# arm_v2.net
KiCad netlist of a schematic drawn in Altium Designer
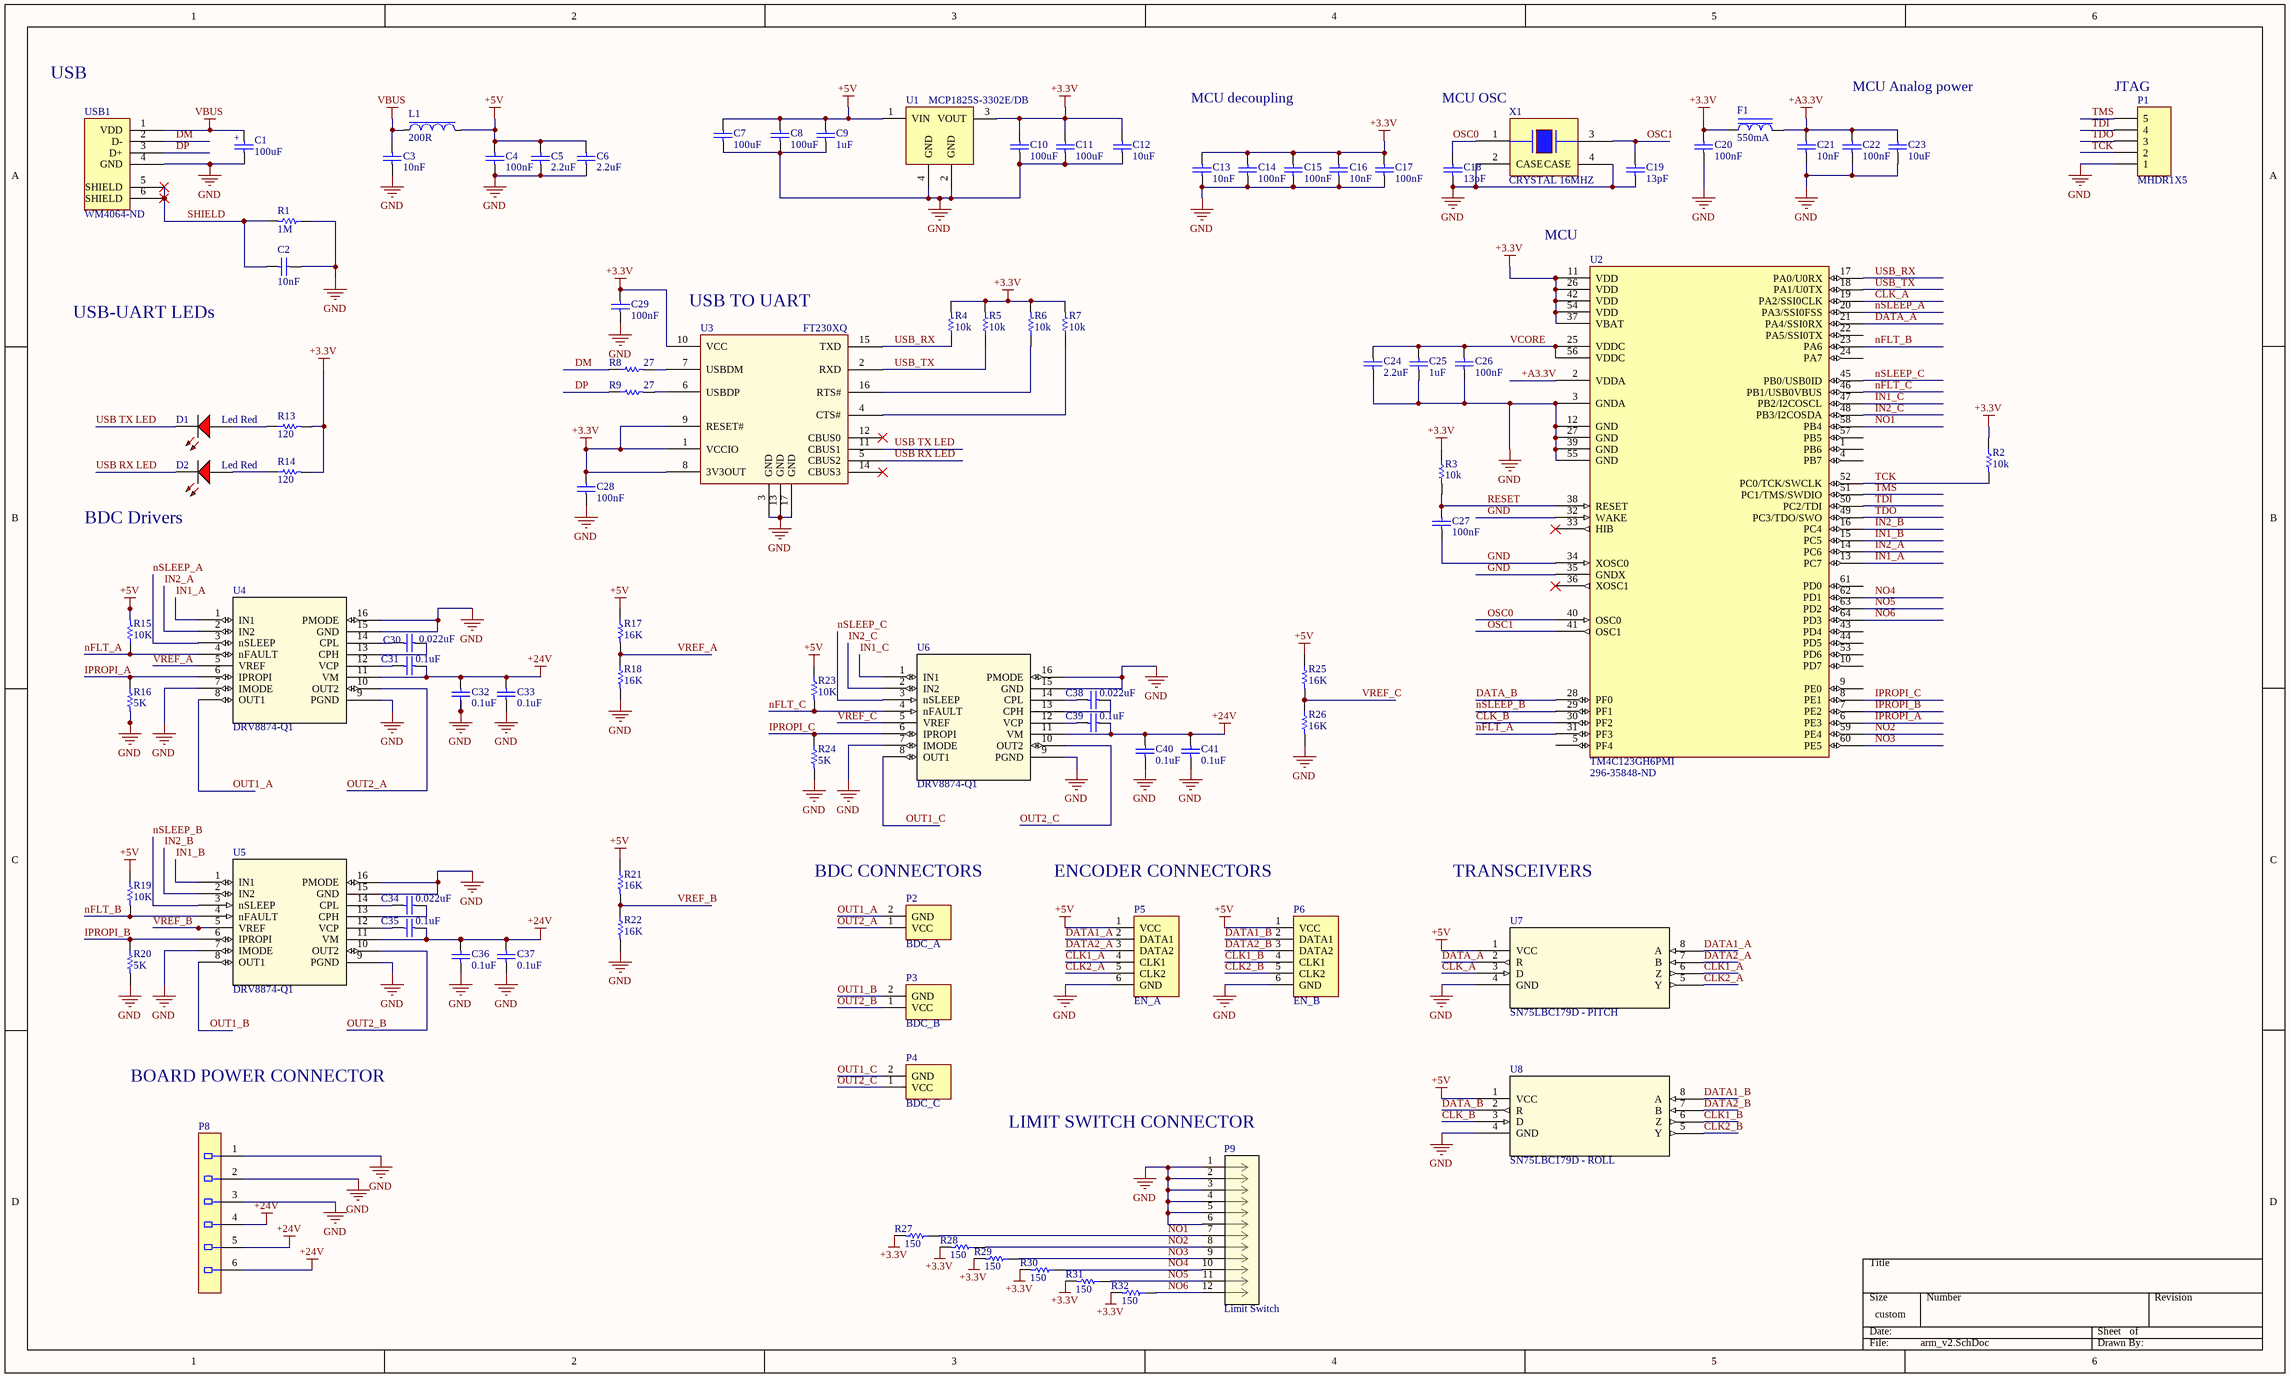
[diagram p0: arm_v2.SchDoc]

(export (version "E")
  (design (tool "Eeschema 10.0.6"))
  (components
    (comp (ref "C1")
      (value "100uF")
      (footprint "CapAlu6.3mmx12.5mm")
      (description "Capacitor 35v 100uF 6.3mm")
      (fields
        (field (name "MANUFACTURER") "Nichicon")
        (field (name "MANUFACTURER PART NUMBER") "UHV1V101MED")
      )
      (libsource (lib "Capacitors") (part "100uF_35v_6.3x12.5"))
    )
    (comp (ref "C2")
      (value "10nF")
      (footprint "CAP_1206")
      (description "CAP CER 10000PF 500V X7R 1206")
      (fields
        (field (name "MANUFACTURER") "Samsung Electro-Mechanics America, Inc")
        (field (name "MANUFACTURER PART NUMBER") "CL31B103KGFNNNE")
      )
      (libsource (lib "Capacitors") (part "10nF_500V_1206"))
    )
    (comp (ref "C3")
      (value "10nF")
      (footprint "CAP_0402_M")
      (description "CAP CER 10000PF 50V 10% X7R 0402")
      (fields
        (field (name "MANUFACTURER") "Kemet")
        (field (name "MANUFACTURER PART NUMBER") "C0402C103K5RACTU")
      )
      (libsource (lib "Capacitors") (part "10nF_50V_0402"))
    )
    (comp (ref "C4")
      (value "100nF")
      (footprint "CAP_0402_M")
      (description "CAP CER 100NF 50V 20% X5R 0402")
      (fields
        (field (name "MANUFACTURER") "TDK Corporation")
        (field (name "MANUFACTURER PART NUMBER") "C1005X5R1H104M050BB")
      )
      (libsource (lib "Capacitors") (part "100nF_50V_0402"))
    )
    (comp (ref "C5")
      (value "2.2uF")
      (footprint "CAP_0402_M")
      (description "CAP CER 2.2UF 10V 20% X5R 0402")
      (fields
        (field (name "MANUFACTURER") "Taiyo Yuden")
        (field (name "MANUFACTURER PART NUMBER") "LMK105BJ225MV-F")
      )
      (libsource (lib "Capacitors") (part "2.2uF_10V_0402"))
    )
    (comp (ref "C6")
      (value "2.2uF")
      (footprint "CAP_0402_M")
      (description "CAP CER 2.2UF 10V 20% X5R 0402")
      (fields
        (field (name "MANUFACTURER") "Taiyo Yuden")
        (field (name "MANUFACTURER PART NUMBER") "LMK105BJ225MV-F")
      )
      (libsource (lib "Capacitors") (part "2.2uF_10V_0402"))
    )
    (comp (ref "C7")
      (value "100uF")
      (footprint "CAP_1206")
      (description "CAP CER 100UF 6.3V X5R 1206")
      (fields
        (field (name "MANUFACTURER") "Murata Electronics North America")
        (field (name "MANUFACTURER PART NUMBER") "GRM31CR60J107ME39L")
      )
      (libsource (lib "Capacitors") (part "100uF_6.3v_1206_X5R"))
    )
    (comp (ref "C8")
      (value "100uF")
      (footprint "CAP_1206")
      (description "CAP CER 100UF 6.3V X5R 1206")
      (fields
        (field (name "MANUFACTURER") "Murata Electronics North America")
        (field (name "MANUFACTURER PART NUMBER") "GRM31CR60J107ME39L")
      )
      (libsource (lib "Capacitors") (part "100uF_6.3v_1206_X5R"))
    )
    (comp (ref "C9")
      (value "1uF")
      (footprint "CAP_0402_M")
      (description "CAP CER 1UF 25V 10% X5R 0402")
      (fields
        (field (name "MANUFACTURER") "TDK Corporation")
        (field (name "MANUFACTURER PART NUMBER") "C1005X5R1E105K050BC")
      )
      (libsource (lib "Capacitors") (part "1uF_25V_0402"))
    )
    (comp (ref "C10")
      (value "100uF")
      (footprint "CAP_1206")
      (description "CAP CER 100UF 6.3V X5R 1206")
      (fields
        (field (name "MANUFACTURER") "Murata Electronics North America")
        (field (name "MANUFACTURER PART NUMBER") "GRM31CR60J107ME39L")
      )
      (libsource (lib "Capacitors") (part "100uF_6.3v_1206_X5R"))
    )
    (comp (ref "C11")
      (value "100uF")
      (footprint "CAP_1206")
      (description "CAP CER 100UF 6.3V X5R 1206")
      (fields
        (field (name "MANUFACTURER") "Murata Electronics North America")
        (field (name "MANUFACTURER PART NUMBER") "GRM31CR60J107ME39L")
      )
      (libsource (lib "Capacitors") (part "100uF_6.3v_1206_X5R"))
    )
    (comp (ref "C12")
      (value "10uF")
      (footprint "CAP_0603")
      (description "CAP CER 10UF 10V 20% X5R 0603")
      (fields
        (field (name "MANUFACTURER") "Taiyo Yuden")
        (field (name "MANUFACTURER PART NUMBER") "LMK107BBJ106MAHT")
      )
      (libsource (lib "Capacitors") (part "10uF_10V_0603"))
    )
    (comp (ref "C13")
      (value "10nF")
      (footprint "CAP_0402_M")
      (description "CAP CER 10000PF 50V 10% X7R 0402")
      (fields
        (field (name "MANUFACTURER") "Kemet")
        (field (name "MANUFACTURER PART NUMBER") "C0402C103K5RACTU")
      )
      (libsource (lib "Capacitors") (part "10nF_50V_0402"))
    )
    (comp (ref "C14")
      (value "100nF")
      (footprint "CAP_0402_M")
      (description "CAP CER 100NF 50V 20% X5R 0402")
      (fields
        (field (name "MANUFACTURER") "TDK Corporation")
        (field (name "MANUFACTURER PART NUMBER") "C1005X5R1H104M050BB")
      )
      (libsource (lib "Capacitors") (part "100nF_50V_0402"))
    )
    (comp (ref "C15")
      (value "100nF")
      (footprint "CAP_0402_M")
      (description "CAP CER 100NF 50V 20% X5R 0402")
      (fields
        (field (name "MANUFACTURER") "TDK Corporation")
        (field (name "MANUFACTURER PART NUMBER") "C1005X5R1H104M050BB")
      )
      (libsource (lib "Capacitors") (part "100nF_50V_0402"))
    )
    (comp (ref "C16")
      (value "10nF")
      (footprint "CAP_0402_M")
      (description "CAP CER 10000PF 50V 10% X7R 0402")
      (fields
        (field (name "MANUFACTURER") "Kemet")
        (field (name "MANUFACTURER PART NUMBER") "C0402C103K5RACTU")
      )
      (libsource (lib "Capacitors") (part "10nF_50V_0402"))
    )
    (comp (ref "C17")
      (value "100nF")
      (footprint "CAP_0402_M")
      (description "CAP CER 100NF 50V 20% X5R 0402")
      (fields
        (field (name "MANUFACTURER") "TDK Corporation")
        (field (name "MANUFACTURER PART NUMBER") "C1005X5R1H104M050BB")
      )
      (libsource (lib "Capacitors") (part "100nF_50V_0402"))
    )
    (comp (ref "C18")
      (value "13pF")
      (footprint "CAP_0402_M")
      (description "CAP CER 13PF 50V 5% NP0 0402")
      (fields
        (field (name "MANUFACTURER") "Samsung Electro-Mechanics America, Inc")
        (field (name "MANUFACTURER PART NUMBER") "CL05C130JB5NNNC")
      )
      (libsource (lib "Capacitors") (part "13pF_50V_0402"))
    )
    (comp (ref "C19")
      (value "13pF")
      (footprint "CAP_0402_M")
      (description "CAP CER 13PF 50V 5% NP0 0402")
      (fields
        (field (name "MANUFACTURER") "Samsung Electro-Mechanics America, Inc")
        (field (name "MANUFACTURER PART NUMBER") "CL05C130JB5NNNC")
      )
      (libsource (lib "Capacitors") (part "13pF_50V_0402"))
    )
    (comp (ref "C20")
      (value "100nF")
      (footprint "CAP_0402_M")
      (description "CAP CER 100NF 50V 20% X5R 0402")
      (fields
        (field (name "MANUFACTURER") "TDK Corporation")
        (field (name "MANUFACTURER PART NUMBER") "C1005X5R1H104M050BB")
      )
      (libsource (lib "Capacitors") (part "100nF_50V_0402"))
    )
    (comp (ref "C21")
      (value "10nF")
      (footprint "CAP_0402_M")
      (description "CAP CER 10000PF 50V 10% X7R 0402")
      (fields
        (field (name "MANUFACTURER") "Kemet")
        (field (name "MANUFACTURER PART NUMBER") "C0402C103K5RACTU")
      )
      (libsource (lib "Capacitors") (part "10nF_50V_0402"))
    )
    (comp (ref "C22")
      (value "100nF")
      (footprint "CAP_0402_M")
      (description "CAP CER 100NF 50V 20% X5R 0402")
      (fields
        (field (name "MANUFACTURER") "TDK Corporation")
        (field (name "MANUFACTURER PART NUMBER") "C1005X5R1H104M050BB")
      )
      (libsource (lib "Capacitors") (part "100nF_50V_0402"))
    )
    (comp (ref "C23")
      (value "10uF")
      (footprint "CAP_0603")
      (description "CAP CER 10UF 10V 20% X5R 0603")
      (fields
        (field (name "MANUFACTURER") "Taiyo Yuden")
        (field (name "MANUFACTURER PART NUMBER") "LMK107BBJ106MAHT")
      )
      (libsource (lib "Capacitors") (part "10uF_10V_0603"))
    )
    (comp (ref "C24")
      (value "2.2uF")
      (footprint "CAP_0603")
      (description "CAP CER 2.2UF 35V 10% X5R 0603")
      (fields
        (field (name "MANUFACTURER") "Murata Electronics North America")
        (field (name "MANUFACTURER PART NUMBER") "GRM188R6YA225KA12D")
      )
      (libsource (lib "Capacitors") (part "2.2uF_35V_0603"))
    )
    (comp (ref "C25")
      (value "1uF")
      (footprint "CAP_0402_M")
      (description "CAP CER 1UF 25V 10% X5R 0402")
      (fields
        (field (name "MANUFACTURER") "TDK Corporation")
        (field (name "MANUFACTURER PART NUMBER") "C1005X5R1E105K050BC")
      )
      (libsource (lib "Capacitors") (part "1uF_25V_0402"))
    )
    (comp (ref "C26")
      (value "100nF")
      (footprint "CAP_0402_M")
      (description "CAP CER 100NF 50V 20% X5R 0402")
      (fields
        (field (name "MANUFACTURER") "TDK Corporation")
        (field (name "MANUFACTURER PART NUMBER") "C1005X5R1H104M050BB")
      )
      (libsource (lib "Capacitors") (part "100nF_50V_0402"))
    )
    (comp (ref "C27")
      (value "100nF")
      (footprint "CAP_0402_M")
      (description "CAP CER 100NF 50V 20% X5R 0402")
      (fields
        (field (name "MANUFACTURER") "TDK Corporation")
        (field (name "MANUFACTURER PART NUMBER") "C1005X5R1H104M050BB")
      )
      (libsource (lib "Capacitors") (part "100nF_50V_0402"))
    )
    (comp (ref "C28")
      (value "100nF")
      (footprint "CAP_0402_M")
      (description "CAP CER 100NF 50V 20% X5R 0402")
      (fields
        (field (name "MANUFACTURER") "TDK Corporation")
        (field (name "MANUFACTURER PART NUMBER") "C1005X5R1H104M050BB")
      )
      (libsource (lib "Capacitors") (part "100nF_50V_0402"))
    )
    (comp (ref "C29")
      (value "100nF")
      (footprint "CAP_0402_M")
      (description "CAP CER 100NF 50V 20% X5R 0402")
      (fields
        (field (name "MANUFACTURER") "TDK Corporation")
        (field (name "MANUFACTURER PART NUMBER") "C1005X5R1H104M050BB")
      )
      (libsource (lib "Capacitors") (part "100nF_50V_0402"))
    )
    (comp (ref "C30")
      (value "0.022uF")
      (footprint "CAP_0402_M")
      (description "CAP CER 100NF 50V 20% X5R 0402")
      (fields
        (field (name "MANUFACTURER") "TDK Corporation")
        (field (name "MANUFACTURER PART NUMBER") "C1005X5R1H104M050BB")
      )
      (libsource (lib "Capacitors") (part "100nF_50V_0402"))
    )
    (comp (ref "C31")
      (value "0.1uF")
      (footprint "CAP_0402_M")
      (description "CAP CER 100NF 50V 20% X5R 0402")
      (fields
        (field (name "MANUFACTURER") "TDK Corporation")
        (field (name "MANUFACTURER PART NUMBER") "C1005X5R1H104M050BB")
      )
      (libsource (lib "Capacitors") (part "100nF_50V_0402"))
    )
    (comp (ref "C32")
      (value "0.1uF")
      (footprint "CAP_0402_M")
      (description "CAP CER 100NF 50V 20% X5R 0402")
      (fields
        (field (name "MANUFACTURER") "TDK Corporation")
        (field (name "MANUFACTURER PART NUMBER") "C1005X5R1H104M050BB")
      )
      (libsource (lib "Capacitors") (part "100nF_50V_0402"))
    )
    (comp (ref "C33")
      (value "0.1uF")
      (footprint "CAP_0402_M")
      (description "CAP CER 100NF 50V 20% X5R 0402")
      (fields
        (field (name "MANUFACTURER") "TDK Corporation")
        (field (name "MANUFACTURER PART NUMBER") "C1005X5R1H104M050BB")
      )
      (libsource (lib "Capacitors") (part "100nF_50V_0402"))
    )
    (comp (ref "C34")
      (value "0.022uF")
      (footprint "CAP_0402_M")
      (description "CAP CER 100NF 50V 20% X5R 0402")
      (fields
        (field (name "MANUFACTURER") "TDK Corporation")
        (field (name "MANUFACTURER PART NUMBER") "C1005X5R1H104M050BB")
      )
      (libsource (lib "Capacitors") (part "100nF_50V_0402"))
    )
    (comp (ref "C35")
      (value "0.1uF")
      (footprint "CAP_0402_M")
      (description "CAP CER 100NF 50V 20% X5R 0402")
      (fields
        (field (name "MANUFACTURER") "TDK Corporation")
        (field (name "MANUFACTURER PART NUMBER") "C1005X5R1H104M050BB")
      )
      (libsource (lib "Capacitors") (part "100nF_50V_0402"))
    )
    (comp (ref "C36")
      (value "0.1uF")
      (footprint "CAP_0402_M")
      (description "CAP CER 100NF 50V 20% X5R 0402")
      (fields
        (field (name "MANUFACTURER") "TDK Corporation")
        (field (name "MANUFACTURER PART NUMBER") "C1005X5R1H104M050BB")
      )
      (libsource (lib "Capacitors") (part "100nF_50V_0402"))
    )
    (comp (ref "C37")
      (value "0.1uF")
      (footprint "CAP_0402_M")
      (description "CAP CER 100NF 50V 20% X5R 0402")
      (fields
        (field (name "MANUFACTURER") "TDK Corporation")
        (field (name "MANUFACTURER PART NUMBER") "C1005X5R1H104M050BB")
      )
      (libsource (lib "Capacitors") (part "100nF_50V_0402"))
    )
    (comp (ref "C38")
      (value "0.022uF")
      (footprint "CAP_0402_M")
      (description "CAP CER 100NF 50V 20% X5R 0402")
      (fields
        (field (name "MANUFACTURER") "TDK Corporation")
        (field (name "MANUFACTURER PART NUMBER") "C1005X5R1H104M050BB")
      )
      (libsource (lib "Capacitors") (part "100nF_50V_0402"))
    )
    (comp (ref "C39")
      (value "0.1uF")
      (footprint "CAP_0402_M")
      (description "CAP CER 100NF 50V 20% X5R 0402")
      (fields
        (field (name "MANUFACTURER") "TDK Corporation")
        (field (name "MANUFACTURER PART NUMBER") "C1005X5R1H104M050BB")
      )
      (libsource (lib "Capacitors") (part "100nF_50V_0402"))
    )
    (comp (ref "C40")
      (value "0.1uF")
      (footprint "CAP_0402_M")
      (description "CAP CER 100NF 50V 20% X5R 0402")
      (fields
        (field (name "MANUFACTURER") "TDK Corporation")
        (field (name "MANUFACTURER PART NUMBER") "C1005X5R1H104M050BB")
      )
      (libsource (lib "Capacitors") (part "100nF_50V_0402"))
    )
    (comp (ref "C41")
      (value "0.1uF")
      (footprint "CAP_0402_M")
      (description "CAP CER 100NF 50V 20% X5R 0402")
      (fields
        (field (name "MANUFACTURER") "TDK Corporation")
        (field (name "MANUFACTURER PART NUMBER") "C1005X5R1H104M050BB")
      )
      (libsource (lib "Capacitors") (part "100nF_50V_0402"))
    )
    (comp (ref "D1")
      (value "Led Red")
      (footprint "TOPLED 0805")
      (description "LED TOPLED 630NM SUP RED CLR SMD")
      (fields
        (field (name "MANUFACTURER") "OSRAM Opto Semiconductors Inc")
        (field (name "MANUFACTURER PART NUMBER") "LS M67K-H2L1-1-Z")
      )
      (libsource (lib "Diodes") (part "TOPLED 0803"))
    )
    (comp (ref "D2")
      (value "Led Red")
      (footprint "TOPLED 0805")
      (description "LED TOPLED 630NM SUP RED CLR SMD")
      (fields
        (field (name "MANUFACTURER") "OSRAM Opto Semiconductors Inc")
        (field (name "MANUFACTURER PART NUMBER") "LS M67K-H2L1-1-Z")
      )
      (libsource (lib "Diodes") (part "TOPLED 0803"))
    )
    (comp (ref "F1")
      (value "550mA")
      (footprint "RES_0402_M")
      (description "FERRITE CHIP 40 OHM 550MA 0402")
      (fields
        (field (name "MANUFACTURER") "TDK Corporation")
        (field (name "MANUFACTURER PART NUMBER") "MMZ1005Y400CT000")
      )
      (libsource (lib "Resistors") (part "40O_550mA_0402"))
    )
    (comp (ref "L1")
      (value "200R")
      (footprint "IND_0603")
      (description "FILTER CHIP 220 OHM 2A 0603")
      (fields
        (field (name "MANUFACTURER") "Murata Electronics North America")
        (field (name "MANUFACTURER PART NUMBER") "BLM18EG221SN1D")
      )
      (libsource (lib "Inductors") (part "Ferrite_200 ohms_2A"))
    )
    (comp (ref "P1")
      (value "MHDR1X5")
      (footprint "MHDR1X5")
      (description "Header, 5-Pin")
      (fields (field (name "PUBLISHER") "Altium Limited"))
      (libsource (lib "Miscellaneous Connectors") (part "MHDR1X5"))
    )
    (comp (ref "P2")
      (value "BDC_A")
      (footprint "SamacSys:436500227")
      (description "Connector")
      (fields (field (name "MANUFACTURER_PART_NUMBER") "43650-0227"))
      (libsource (lib "*") (part "43650-0227"))
    )
    (comp (ref "P3")
      (value "BDC_B")
      (footprint "SamacSys:436500227")
      (description "Connector")
      (fields (field (name "MANUFACTURER_PART_NUMBER") "43650-0227"))
      (libsource (lib "*") (part "43650-0227"))
    )
    (comp (ref "P4")
      (value "BDC_C")
      (footprint "SamacSys:436500227")
      (description "Connector")
      (fields (field (name "MANUFACTURER_PART_NUMBER") "43650-0227"))
      (libsource (lib "*") (part "43650-0227"))
    )
    (comp (ref "P5")
      (value "EN_A")
      (footprint "SamacSys:1053091106")
      (description "Connector")
      (fields (field (name "MANUFACTURER_PART_NUMBER") "105309-1106"))
      (libsource (lib "*") (part "105309-1106"))
    )
    (comp (ref "P6")
      (value "EN_B")
      (footprint "SamacSys:1053091106")
      (description "Connector")
      (fields (field (name "MANUFACTURER_PART_NUMBER") "105309-1106"))
      (libsource (lib "*") (part "105309-1106"))
    )
    (comp (ref "P8") (value "76825-0006") (libsource (lib "Molex 76825-0006") (part "76825-0006")))
    (comp (ref "P9")
      (value "Limit Switch")
      (footprint "CON_1053141112")
      (description "No Description Available")
      (fields
        (field (name "MANUFACTURER_PART_NUMBER") "1053141112")
        (field (name "COPYRIGHT") "Copyright (C) 2018 Accelerated Designs. All rights reserved")
      )
      (libsource (lib "Molex 1053141112") (part "1053141112"))
    )
    (comp (ref "R1")
      (value "1M")
      (footprint "RES_1206")
      (description "RES SMD 1M OHM 5% 1/4W 1206")
      (fields
        (field (name "MANUFACTURER") "Panasonic Electronic Components")
        (field (name "MANUFACTURER PART NUMBER") "ERJ-8GEYJ105V")
      )
      (libsource (lib "Resistors") (part "1M_5%_1206"))
    )
    (comp (ref "R2")
      (value "10k")
      (footprint "RES_0402_M")
      (description "RES SMD 10K OHM 1% 1/10W 0402")
      (fields
        (field (name "MANUFACTURER") "Panasonic Electronic Components")
        (field (name "MANUFACTURER PART NUMBER") "ERJ-2RKF1002X")
      )
      (libsource (lib "Resistors") (part "10k_1%_0402"))
    )
    (comp (ref "R3")
      (value "10k")
      (footprint "RES_0402_M")
      (description "RES SMD 10K OHM 1% 1/10W 0402")
      (fields
        (field (name "MANUFACTURER") "Panasonic Electronic Components")
        (field (name "MANUFACTURER PART NUMBER") "ERJ-2RKF1002X")
      )
      (libsource (lib "Resistors") (part "10k_1%_0402"))
    )
    (comp (ref "R4")
      (value "10k")
      (footprint "RES_0402_M")
      (description "RES SMD 10K OHM 1% 1/10W 0402")
      (fields
        (field (name "MANUFACTURER") "Panasonic Electronic Components")
        (field (name "MANUFACTURER PART NUMBER") "ERJ-2RKF1002X")
      )
      (libsource (lib "Resistors") (part "10k_1%_0402"))
    )
    (comp (ref "R5")
      (value "10k")
      (footprint "RES_0402_M")
      (description "RES SMD 10K OHM 1% 1/10W 0402")
      (fields
        (field (name "MANUFACTURER") "Panasonic Electronic Components")
        (field (name "MANUFACTURER PART NUMBER") "ERJ-2RKF1002X")
      )
      (libsource (lib "Resistors") (part "10k_1%_0402"))
    )
    (comp (ref "R6")
      (value "10k")
      (footprint "RES_0402_M")
      (description "RES SMD 10K OHM 1% 1/10W 0402")
      (fields
        (field (name "MANUFACTURER") "Panasonic Electronic Components")
        (field (name "MANUFACTURER PART NUMBER") "ERJ-2RKF1002X")
      )
      (libsource (lib "Resistors") (part "10k_1%_0402"))
    )
    (comp (ref "R7")
      (value "10k")
      (footprint "RES_0402_M")
      (description "RES SMD 10K OHM 1% 1/10W 0402")
      (fields
        (field (name "MANUFACTURER") "Panasonic Electronic Components")
        (field (name "MANUFACTURER PART NUMBER") "ERJ-2RKF1002X")
      )
      (libsource (lib "Resistors") (part "10k_1%_0402"))
    )
    (comp (ref "R8")
      (value "27")
      (footprint "RES_0402_M")
      (description "RES SMD 27 OHM 1% 1/10W 0402")
      (fields
        (field (name "MANUFACTURER") "Panasonic Electronic Components")
        (field (name "MANUFACTURER PART NUMBER") "ERJ-2RKF27R0X")
      )
      (libsource (lib "Resistors") (part "27_1%_0402"))
    )
    (comp (ref "R9")
      (value "27")
      (footprint "RES_0402_M")
      (description "RES SMD 27 OHM 1% 1/10W 0402")
      (fields
        (field (name "MANUFACTURER") "Panasonic Electronic Components")
        (field (name "MANUFACTURER PART NUMBER") "ERJ-2RKF27R0X")
      )
      (libsource (lib "Resistors") (part "27_1%_0402"))
    )
    (comp (ref "R13")
      (value "120")
      (footprint "RES_0402_M")
      (description "RES SMD 120 OHM 1% 1/10W 0402")
      (fields
        (field (name "MANUFACTURER") "Panasonic Electronic Components")
        (field (name "MANUFACTURER PART NUMBER") "ERJ-2RKF1200X")
      )
      (libsource (lib "Resistors") (part "120_1%_0402"))
    )
    (comp (ref "R14")
      (value "120")
      (footprint "RES_0402_M")
      (description "RES SMD 120 OHM 1% 1/10W 0402")
      (fields
        (field (name "MANUFACTURER") "Panasonic Electronic Components")
        (field (name "MANUFACTURER PART NUMBER") "ERJ-2RKF1200X")
      )
      (libsource (lib "Resistors") (part "120_1%_0402"))
    )
    (comp (ref "R15")
      (value "10K")
      (footprint "RES_0402_M")
      (description "RES SMD 0 OHM JUMPER 1/16W 0402")
      (fields
        (field (name "MANUFACTURER") "Yageo")
        (field (name "MANUFACTURER PART NUMBER") "RC0402FR-070RL")
      )
      (libsource (lib "Resistors") (part "0_0402"))
    )
    (comp (ref "R16")
      (value "5K")
      (footprint "RES_0402_M")
      (description "RES SMD 0 OHM JUMPER 1/16W 0402")
      (fields
        (field (name "MANUFACTURER") "Yageo")
        (field (name "MANUFACTURER PART NUMBER") "RC0402FR-070RL")
      )
      (libsource (lib "Resistors") (part "0_0402"))
    )
    (comp (ref "R17")
      (value "16K")
      (footprint "RES_0402_M")
      (description "RES SMD 0 OHM JUMPER 1/16W 0402")
      (fields
        (field (name "MANUFACTURER") "Yageo")
        (field (name "MANUFACTURER PART NUMBER") "RC0402FR-070RL")
      )
      (libsource (lib "Resistors") (part "0_0402"))
    )
    (comp (ref "R18")
      (value "16K")
      (footprint "RES_0402_M")
      (description "RES SMD 0 OHM JUMPER 1/16W 0402")
      (fields
        (field (name "MANUFACTURER") "Yageo")
        (field (name "MANUFACTURER PART NUMBER") "RC0402FR-070RL")
      )
      (libsource (lib "Resistors") (part "0_0402"))
    )
    (comp (ref "R19")
      (value "10K")
      (footprint "RES_0402_M")
      (description "RES SMD 0 OHM JUMPER 1/16W 0402")
      (fields
        (field (name "MANUFACTURER") "Yageo")
        (field (name "MANUFACTURER PART NUMBER") "RC0402FR-070RL")
      )
      (libsource (lib "Resistors") (part "0_0402"))
    )
    (comp (ref "R20")
      (value "5K")
      (footprint "RES_0402_M")
      (description "RES SMD 0 OHM JUMPER 1/16W 0402")
      (fields
        (field (name "MANUFACTURER") "Yageo")
        (field (name "MANUFACTURER PART NUMBER") "RC0402FR-070RL")
      )
      (libsource (lib "Resistors") (part "0_0402"))
    )
    (comp (ref "R21")
      (value "16K")
      (footprint "RES_0402_M")
      (description "RES SMD 0 OHM JUMPER 1/16W 0402")
      (fields
        (field (name "MANUFACTURER") "Yageo")
        (field (name "MANUFACTURER PART NUMBER") "RC0402FR-070RL")
      )
      (libsource (lib "Resistors") (part "0_0402"))
    )
    (comp (ref "R22")
      (value "16K")
      (footprint "RES_0402_M")
      (description "RES SMD 0 OHM JUMPER 1/16W 0402")
      (fields
        (field (name "MANUFACTURER") "Yageo")
        (field (name "MANUFACTURER PART NUMBER") "RC0402FR-070RL")
      )
      (libsource (lib "Resistors") (part "0_0402"))
    )
    (comp (ref "R23")
      (value "10K")
      (footprint "RES_0402_M")
      (description "RES SMD 0 OHM JUMPER 1/16W 0402")
      (fields
        (field (name "MANUFACTURER") "Yageo")
        (field (name "MANUFACTURER PART NUMBER") "RC0402FR-070RL")
      )
      (libsource (lib "Resistors") (part "0_0402"))
    )
    (comp (ref "R24")
      (value "5K")
      (footprint "RES_0402_M")
      (description "RES SMD 0 OHM JUMPER 1/16W 0402")
      (fields
        (field (name "MANUFACTURER") "Yageo")
        (field (name "MANUFACTURER PART NUMBER") "RC0402FR-070RL")
      )
      (libsource (lib "Resistors") (part "0_0402"))
    )
    (comp (ref "R25")
      (value "16K")
      (footprint "RES_0402_M")
      (description "RES SMD 0 OHM JUMPER 1/16W 0402")
      (fields
        (field (name "MANUFACTURER") "Yageo")
        (field (name "MANUFACTURER PART NUMBER") "RC0402FR-070RL")
      )
      (libsource (lib "Resistors") (part "0_0402"))
    )
    (comp (ref "R26")
      (value "16K")
      (footprint "RES_0402_M")
      (description "RES SMD 0 OHM JUMPER 1/16W 0402")
      (fields
        (field (name "MANUFACTURER") "Yageo")
        (field (name "MANUFACTURER PART NUMBER") "RC0402FR-070RL")
      )
      (libsource (lib "Resistors") (part "0_0402"))
    )
    (comp (ref "R27")
      (value "150")
      (footprint "RES_0402_M")
      (description "RES SMD 10K OHM 1% 1/10W 0402")
      (fields
        (field (name "MANUFACTURER") "Panasonic Electronic Components")
        (field (name "MANUFACTURER PART NUMBER") "ERJ-2RKF1002X")
      )
      (libsource (lib "Resistors") (part "10k_1%_0402"))
    )
    (comp (ref "R28")
      (value "150")
      (footprint "RES_0402_M")
      (description "RES SMD 10K OHM 1% 1/10W 0402")
      (fields
        (field (name "MANUFACTURER") "Panasonic Electronic Components")
        (field (name "MANUFACTURER PART NUMBER") "ERJ-2RKF1002X")
      )
      (libsource (lib "Resistors") (part "10k_1%_0402"))
    )
    (comp (ref "R29")
      (value "150")
      (footprint "RES_0402_M")
      (description "RES SMD 10K OHM 1% 1/10W 0402")
      (fields
        (field (name "MANUFACTURER") "Panasonic Electronic Components")
        (field (name "MANUFACTURER PART NUMBER") "ERJ-2RKF1002X")
      )
      (libsource (lib "Resistors") (part "10k_1%_0402"))
    )
    (comp (ref "R30")
      (value "150")
      (footprint "RES_0402_M")
      (description "RES SMD 10K OHM 1% 1/10W 0402")
      (fields
        (field (name "MANUFACTURER") "Panasonic Electronic Components")
        (field (name "MANUFACTURER PART NUMBER") "ERJ-2RKF1002X")
      )
      (libsource (lib "Resistors") (part "10k_1%_0402"))
    )
    (comp (ref "R31")
      (value "150")
      (footprint "RES_0402_M")
      (description "RES SMD 10K OHM 1% 1/10W 0402")
      (fields
        (field (name "MANUFACTURER") "Panasonic Electronic Components")
        (field (name "MANUFACTURER PART NUMBER") "ERJ-2RKF1002X")
      )
      (libsource (lib "Resistors") (part "10k_1%_0402"))
    )
    (comp (ref "R32")
      (value "150")
      (footprint "RES_0402_M")
      (description "RES SMD 10K OHM 1% 1/10W 0402")
      (fields
        (field (name "MANUFACTURER") "Panasonic Electronic Components")
        (field (name "MANUFACTURER PART NUMBER") "ERJ-2RKF1002X")
      )
      (libsource (lib "Resistors") (part "10k_1%_0402"))
    )
    (comp (ref "U1")
      (value "MCP1825S-3302E/DB")
      (footprint "SOT230P700X180-4N")
      (description "500 mA, Low Voltage, Low Quiescent Current LDO Regulator")
      (fields (field (name "MANUFACTURER") "Microchip Technology"))
      (libsource (lib "ICs") (part "MCP1825S-3302E/DB"))
    )
    (comp (ref "U2")
      (value "TM4C123GH6PMI")
      (footprint "TSQFP50P1200X1200X120-64N")
      (description "Tiva TM4C123GH6PM Microcontroller ARM Cortex 80 MHz FPU")
      (fields (field (name "SUPPLIER PART NUMBER 1") "296-35848-ND"))
      (libsource (lib "ICs") (part "TM4C123GH6PMI"))
    )
    (comp (ref "U3")
      (value "FT230XQ")
      (footprint "QFN65P400X400X80_HS-17N")
      (description "IC USB SERIAL BASIC UART 16QFN")
      (fields
        (field (name "MANUFACTURER") "FTDI, Future Technology Devices International Ltd")
        (field (name "MANUFACTURER PART NUMBER") "FT230XQ-R")
      )
      (libsource (lib "ICs") (part "FT230XQ-R"))
    )
    (comp (ref "U4")
      (value "DRV8874-Q1")
      (footprint "SOIC_PWPRQ1_TEX")
      (description "No Description Available")
      (fields
        (field (name "MANUFACTURER_PART_NUMBER") "DRV8876QPWPRQ1")
        (field (name "COPYRIGHT") "Copyright (C) 2018 Accelerated Designs. All rights reserved")
      )
      (libsource (lib "DRV8876") (part "DRV8876QPWPRQ1"))
    )
    (comp (ref "U5")
      (value "DRV8874-Q1")
      (footprint "SOIC_PWPRQ1_TEX")
      (description "No Description Available")
      (fields
        (field (name "MANUFACTURER_PART_NUMBER") "DRV8876QPWPRQ1")
        (field (name "COPYRIGHT") "Copyright (C) 2018 Accelerated Designs. All rights reserved")
      )
      (libsource (lib "DRV8876") (part "DRV8876QPWPRQ1"))
    )
    (comp (ref "U6")
      (value "DRV8874-Q1")
      (footprint "SOIC_PWPRQ1_TEX")
      (description "No Description Available")
      (fields
        (field (name "MANUFACTURER_PART_NUMBER") "DRV8876QPWPRQ1")
        (field (name "COPYRIGHT") "Copyright (C) 2018 Accelerated Designs. All rights reserved")
      )
      (libsource (lib "DRV8876") (part "DRV8876QPWPRQ1"))
    )
    (comp (ref "U7")
      (value "SN75LBC179D - PITCH")
      (footprint "D8")
      (description "Low-Power Differential Line Driver And Receiver Pair")
      (fields
        (field (name "MANUFACTURER") "Texas Instruments")
        (field (name "GENERIC_PART_NUMBER") "SN75LBC179")
        (field (name "COPYRIGHT") "Copyright (C) 2018 Accelerated Designs. All rights reserved")
      )
      (libsource (lib "SN75LBC179DR") (part "SN75LBC179D"))
    )
    (comp (ref "U8")
      (value "SN75LBC179D - ROLL")
      (footprint "D8")
      (description "Low-Power Differential Line Driver And Receiver Pair")
      (fields
        (field (name "MANUFACTURER") "Texas Instruments")
        (field (name "GENERIC_PART_NUMBER") "SN75LBC179")
        (field (name "COPYRIGHT") "Copyright (C) 2018 Accelerated Designs. All rights reserved")
      )
      (libsource (lib "SN75LBC179DR") (part "SN75LBC179D"))
    )
    (comp (ref "USB1")
      (value "USB type-B jack")
      (footprint "USB2.5-2H4E")
      (fields (field (name "SUPPLIER PART NUMBER 1") "WM4064-ND"))
      (libsource (lib "Connectors") (part "MOLEX 0670688010"))
    )
    (comp (ref "X1")
      (value "CRYSTAL 16MHZ")
      (footprint "CRYSTAL_3.2x2.5")
      (description "CRYSTAL 16MHZ 20PF SMD")
      (fields
        (field (name "MANUFACTURER") "CTS-Frequency Controls")
        (field (name "MANUFACTURER PART NUMBER") "403C35E16M00000")
      )
      (libsource (lib "ICs") (part "403C35E16M00000"))
    )
  )
  (nets
    (net (code "1") (name "+3.3V") (class "Default")
      (node (ref "C10") (pin "1") (pinfunction "1_1") (pintype "passive"))
      (node (ref "C11") (pin "1") (pinfunction "1_1") (pintype "passive"))
      (node (ref "C12") (pin "1") (pinfunction "1_1") (pintype "passive"))
      (node (ref "C13") (pin "2") (pinfunction "2_2") (pintype "passive"))
      (node (ref "C14") (pin "2") (pinfunction "2_2") (pintype "passive"))
      (node (ref "C15") (pin "2") (pinfunction "2_2") (pintype "passive"))
      (node (ref "C16") (pin "2") (pinfunction "2_2") (pintype "passive"))
      (node (ref "C17") (pin "2") (pinfunction "2_2") (pintype "passive"))
      (node (ref "C20") (pin "2") (pinfunction "2_2") (pintype "passive"))
      (node (ref "C28") (pin "2") (pinfunction "2_2") (pintype "passive"))
      (node (ref "C29") (pin "2") (pinfunction "2_2") (pintype "passive"))
      (node (ref "F1") (pin "1") (pinfunction "1_1") (pintype "passive"))
      (node (ref "R13") (pin "2") (pinfunction "2_2") (pintype "passive"))
      (node (ref "R14") (pin "2") (pinfunction "2_2") (pintype "passive"))
      (node (ref "R2") (pin "1") (pinfunction "1_1") (pintype "passive"))
      (node (ref "R27") (pin "2") (pinfunction "2_2") (pintype "passive"))
      (node (ref "R28") (pin "2") (pinfunction "2_2") (pintype "passive"))
      (node (ref "R29") (pin "2") (pinfunction "2_2") (pintype "passive"))
      (node (ref "R3") (pin "1") (pinfunction "1_1") (pintype "passive"))
      (node (ref "R30") (pin "2") (pinfunction "2_2") (pintype "passive"))
      (node (ref "R31") (pin "2") (pinfunction "2_2") (pintype "passive"))
      (node (ref "R32") (pin "2") (pinfunction "2_2") (pintype "passive"))
      (node (ref "R4") (pin "2") (pinfunction "2_2") (pintype "passive"))
      (node (ref "R5") (pin "2") (pinfunction "2_2") (pintype "passive"))
      (node (ref "R6") (pin "2") (pinfunction "2_2") (pintype "passive"))
      (node (ref "R7") (pin "2") (pinfunction "2_2") (pintype "passive"))
      (node (ref "U1") (pin "3") (pinfunction "VOUT_3") (pintype "power_in"))
      (node (ref "U2") (pin "11") (pinfunction "VDD_11") (pintype "power_in"))
      (node (ref "U2") (pin "26") (pinfunction "VDD_26") (pintype "power_in"))
      (node (ref "U2") (pin "37") (pinfunction "VBAT_37") (pintype "power_in"))
      (node (ref "U2") (pin "42") (pinfunction "VDD_42") (pintype "power_in"))
      (node (ref "U2") (pin "54") (pinfunction "VDD_54") (pintype "power_in"))
      (node (ref "U3") (pin "1") (pinfunction "VCCIO_1") (pintype "passive"))
      (node (ref "U3") (pin "10") (pinfunction "VCC_10") (pintype "passive"))
      (node (ref "U3") (pin "8") (pinfunction "3V3OUT_8") (pintype "passive"))
      (node (ref "U3") (pin "9") (pinfunction "RESET#_9") (pintype "passive"))
    )
    (net (code "2") (name "+5V") (class "Default")
      (node (ref "C4") (pin "2") (pinfunction "2_2") (pintype "passive"))
      (node (ref "C5") (pin "2") (pinfunction "2_2") (pintype "passive"))
      (node (ref "C6") (pin "2") (pinfunction "2_2") (pintype "passive"))
      (node (ref "C7") (pin "1") (pinfunction "1_1") (pintype "passive"))
      (node (ref "C8") (pin "1") (pinfunction "1_1") (pintype "passive"))
      (node (ref "C9") (pin "2") (pinfunction "2_2") (pintype "passive"))
      (node (ref "L1") (pin "2") (pinfunction "2_2") (pintype "passive"))
      (node (ref "P5") (pin "1") (pinfunction "VCC_1") (pintype "passive"))
      (node (ref "P6") (pin "1") (pinfunction "VCC_1") (pintype "passive"))
      (node (ref "R15") (pin "2") (pinfunction "2_2") (pintype "passive"))
      (node (ref "R17") (pin "1") (pinfunction "1_1") (pintype "passive"))
      (node (ref "R19") (pin "1") (pinfunction "1_1") (pintype "passive"))
      (node (ref "R21") (pin "1") (pinfunction "1_1") (pintype "passive"))
      (node (ref "R23") (pin "1") (pinfunction "1_1") (pintype "passive"))
      (node (ref "R25") (pin "1") (pinfunction "1_1") (pintype "passive"))
      (node (ref "U1") (pin "1") (pinfunction "VIN_1") (pintype "power_in"))
      (node (ref "U7") (pin "1") (pinfunction "VCC_1") (pintype "power_in"))
      (node (ref "U8") (pin "1") (pinfunction "VCC_1") (pintype "power_in"))
    )
    (net (code "3") (name "+24V") (class "Default")
      (node (ref "C31") (pin "2") (pinfunction "2_2") (pintype "passive"))
      (node (ref "C32") (pin "2") (pinfunction "2_2") (pintype "passive"))
      (node (ref "C33") (pin "2") (pinfunction "2_2") (pintype "passive"))
      (node (ref "C35") (pin "2") (pinfunction "2_2") (pintype "passive"))
      (node (ref "C36") (pin "2") (pinfunction "2_2") (pintype "passive"))
      (node (ref "C37") (pin "2") (pinfunction "2_2") (pintype "passive"))
      (node (ref "C39") (pin "2") (pinfunction "2_2") (pintype "passive"))
      (node (ref "C40") (pin "2") (pinfunction "2_2") (pintype "passive"))
      (node (ref "C41") (pin "2") (pinfunction "2_2") (pintype "passive"))
      (node (ref "P8") (pin "4") (pinfunction "4_4") (pintype "passive"))
      (node (ref "P8") (pin "5") (pinfunction "5_5") (pintype "passive"))
      (node (ref "P8") (pin "6") (pinfunction "6_6") (pintype "passive"))
      (node (ref "U4") (pin "11") (pinfunction "VM_11") (pintype "passive"))
      (node (ref "U5") (pin "11") (pinfunction "VM_11") (pintype "passive"))
      (node (ref "U6") (pin "11") (pinfunction "VM_11") (pintype "passive"))
    )
    (net (code "4") (name "+A3.3V") (class "Default")
      (node (ref "C21") (pin "2") (pinfunction "2_2") (pintype "passive"))
      (node (ref "C22") (pin "2") (pinfunction "2_2") (pintype "passive"))
      (node (ref "C23") (pin "2") (pinfunction "2_2") (pintype "passive"))
      (node (ref "F1") (pin "2") (pinfunction "2_2") (pintype "passive"))
      (node (ref "U2") (pin "2") (pinfunction "VDDA_2") (pintype "power_in"))
    )
    (net (code "5") (name "/CLK1_A") (class "Default")
      (node (ref "P5") (pin "4") (pinfunction "CLK1_4") (pintype "passive"))
      (node (ref "U7") (pin "6") (pinfunction "Z_6") (pintype "output"))
    )
    (net (code "6") (name "/CLK1_B") (class "Default")
      (node (ref "P6") (pin "4") (pinfunction "CLK1_4") (pintype "passive"))
      (node (ref "U8") (pin "6") (pinfunction "Z_6") (pintype "output"))
    )
    (net (code "7") (name "/CLK2_A") (class "Default")
      (node (ref "P5") (pin "5") (pinfunction "CLK2_5") (pintype "passive"))
      (node (ref "U7") (pin "5") (pinfunction "Y_5") (pintype "output"))
    )
    (net (code "8") (name "/CLK2_B") (class "Default")
      (node (ref "P6") (pin "5") (pinfunction "CLK2_5") (pintype "passive"))
      (node (ref "U8") (pin "5") (pinfunction "Y_5") (pintype "output"))
    )
    (net (code "9") (name "/CLK_A") (class "Default")
      (node (ref "U2") (pin "19") (pinfunction "PA2/SSI0CLK_19") (pintype "bidirectional"))
      (node (ref "U7") (pin "3") (pinfunction "D_3") (pintype "input"))
    )
    (net (code "10") (name "/CLK_B") (class "Default")
      (node (ref "U2") (pin "30") (pinfunction "PF2_30") (pintype "bidirectional"))
      (node (ref "U8") (pin "3") (pinfunction "D_3") (pintype "input"))
    )
    (net (code "11") (name "/DATA1_A") (class "Default")
      (node (ref "P5") (pin "2") (pinfunction "DATA1_2") (pintype "passive"))
      (node (ref "U7") (pin "8") (pinfunction "A_8") (pintype "input"))
    )
    (net (code "12") (name "/DATA1_B") (class "Default")
      (node (ref "P6") (pin "2") (pinfunction "DATA1_2") (pintype "passive"))
      (node (ref "U8") (pin "8") (pinfunction "A_8") (pintype "input"))
    )
    (net (code "13") (name "/DATA2_A") (class "Default")
      (node (ref "P5") (pin "3") (pinfunction "DATA2_3") (pintype "passive"))
      (node (ref "U7") (pin "7") (pinfunction "B_7") (pintype "input"))
    )
    (net (code "14") (name "/DATA2_B") (class "Default")
      (node (ref "P6") (pin "3") (pinfunction "DATA2_3") (pintype "passive"))
      (node (ref "U8") (pin "7") (pinfunction "B_7") (pintype "input"))
    )
    (net (code "15") (name "/DATA_A") (class "Default")
      (node (ref "U2") (pin "21") (pinfunction "PA4/SSI0RX_21") (pintype "bidirectional"))
      (node (ref "U7") (pin "2") (pinfunction "R_2") (pintype "output"))
    )
    (net (code "16") (name "/DATA_B") (class "Default")
      (node (ref "U2") (pin "28") (pinfunction "PF0_28") (pintype "bidirectional"))
      (node (ref "U8") (pin "2") (pinfunction "R_2") (pintype "output"))
    )
    (net (code "17") (name "/DM") (class "Default")
      (node (ref "R8") (pin "1") (pinfunction "1_1") (pintype "passive"))
      (node (ref "USB1") (pin "2") (pinfunction "D-_2") (pintype "passive"))
    )
    (net (code "18") (name "/DP") (class "Default")
      (node (ref "R9") (pin "1") (pinfunction "1_1") (pintype "passive"))
      (node (ref "USB1") (pin "3") (pinfunction "D+_3") (pintype "passive"))
    )
    (net (code "19") (name "/IN1_A") (class "Default")
      (node (ref "U2") (pin "13") (pinfunction "PC7_13") (pintype "bidirectional"))
      (node (ref "U4") (pin "1") (pinfunction "IN1_1") (pintype "bidirectional"))
    )
    (net (code "20") (name "/IN1_B") (class "Default")
      (node (ref "U2") (pin "15") (pinfunction "PC5_15") (pintype "bidirectional"))
      (node (ref "U5") (pin "1") (pinfunction "IN1_1") (pintype "bidirectional"))
    )
    (net (code "21") (name "/IN1_C") (class "Default")
      (node (ref "U2") (pin "47") (pinfunction "PB2/I2COSCL_47") (pintype "bidirectional"))
      (node (ref "U6") (pin "1") (pinfunction "IN1_1") (pintype "bidirectional"))
    )
    (net (code "22") (name "/IN2_A") (class "Default")
      (node (ref "U2") (pin "14") (pinfunction "PC6_14") (pintype "bidirectional"))
      (node (ref "U4") (pin "2") (pinfunction "IN2_2") (pintype "bidirectional"))
    )
    (net (code "23") (name "/IN2_B") (class "Default")
      (node (ref "U2") (pin "16") (pinfunction "PC4_16") (pintype "bidirectional"))
      (node (ref "U5") (pin "2") (pinfunction "IN2_2") (pintype "bidirectional"))
    )
    (net (code "24") (name "/IN2_C") (class "Default")
      (node (ref "U2") (pin "48") (pinfunction "PB3/I2COSDA_48") (pintype "bidirectional"))
      (node (ref "U6") (pin "2") (pinfunction "IN2_2") (pintype "bidirectional"))
    )
    (net (code "25") (name "/IPROPI_A") (class "Default")
      (node (ref "R16") (pin "1") (pinfunction "1_1") (pintype "passive"))
      (node (ref "U2") (pin "6") (pinfunction "PE3_6") (pintype "bidirectional"))
      (node (ref "U4") (pin "6") (pinfunction "IPROPI_6") (pintype "bidirectional"))
    )
    (net (code "26") (name "/IPROPI_B") (class "Default")
      (node (ref "R20") (pin "1") (pinfunction "1_1") (pintype "passive"))
      (node (ref "U2") (pin "7") (pinfunction "PE2_7") (pintype "bidirectional"))
      (node (ref "U5") (pin "6") (pinfunction "IPROPI_6") (pintype "bidirectional"))
    )
    (net (code "27") (name "/IPROPI_C") (class "Default")
      (node (ref "R24") (pin "1") (pinfunction "1_1") (pintype "passive"))
      (node (ref "U2") (pin "8") (pinfunction "PE1_8") (pintype "bidirectional"))
      (node (ref "U6") (pin "6") (pinfunction "IPROPI_6") (pintype "bidirectional"))
    )
    (net (code "28") (name "/NO1") (class "Default")
      (node (ref "P9") (pin "7") (pinfunction "7_7") (pintype "passive"))
      (node (ref "R27") (pin "1") (pinfunction "1_1") (pintype "passive"))
      (node (ref "U2") (pin "58") (pinfunction "PB4_58") (pintype "bidirectional"))
    )
    (net (code "29") (name "/NO2") (class "Default")
      (node (ref "P9") (pin "8") (pinfunction "8_8") (pintype "passive"))
      (node (ref "R28") (pin "1") (pinfunction "1_1") (pintype "passive"))
      (node (ref "U2") (pin "59") (pinfunction "PE4_59") (pintype "bidirectional"))
    )
    (net (code "30") (name "/NO3") (class "Default")
      (node (ref "P9") (pin "9") (pinfunction "9_9") (pintype "passive"))
      (node (ref "R29") (pin "1") (pinfunction "1_1") (pintype "passive"))
      (node (ref "U2") (pin "60") (pinfunction "PE5_60") (pintype "bidirectional"))
    )
    (net (code "31") (name "/NO4") (class "Default")
      (node (ref "P9") (pin "10") (pinfunction "10_10") (pintype "passive"))
      (node (ref "R30") (pin "1") (pinfunction "1_1") (pintype "passive"))
      (node (ref "U2") (pin "62") (pinfunction "PD1_62") (pintype "bidirectional"))
    )
    (net (code "32") (name "/NO5") (class "Default")
      (node (ref "P9") (pin "11") (pinfunction "11_11") (pintype "passive"))
      (node (ref "R31") (pin "1") (pinfunction "1_1") (pintype "passive"))
      (node (ref "U2") (pin "63") (pinfunction "PD2_63") (pintype "bidirectional"))
    )
    (net (code "33") (name "/NO6") (class "Default")
      (node (ref "P9") (pin "12") (pinfunction "12_12") (pintype "passive"))
      (node (ref "R32") (pin "1") (pinfunction "1_1") (pintype "passive"))
      (node (ref "U2") (pin "64") (pinfunction "PD3_64") (pintype "bidirectional"))
    )
    (net (code "34") (name "/OSC0") (class "Default")
      (node (ref "C18") (pin "2") (pinfunction "2_2") (pintype "passive"))
      (node (ref "U2") (pin "40") (pinfunction "OSC0_40") (pintype "input"))
      (node (ref "X1") (pin "1") (pintype "passive"))
    )
    (net (code "35") (name "/OSC1") (class "Default")
      (node (ref "C19") (pin "2") (pinfunction "2_2") (pintype "passive"))
      (node (ref "U2") (pin "41") (pinfunction "OSC1_41") (pintype "output"))
      (node (ref "X1") (pin "3") (pintype "passive"))
    )
    (net (code "36") (name "/OUT1_A") (class "Default")
      (node (ref "P2") (pin "2") (pinfunction "GND_2") (pintype "passive"))
      (node (ref "U4") (pin "8") (pinfunction "OUT1_8") (pintype "bidirectional"))
    )
    (net (code "37") (name "/OUT1_B") (class "Default")
      (node (ref "P3") (pin "2") (pinfunction "GND_2") (pintype "passive"))
      (node (ref "U5") (pin "8") (pinfunction "OUT1_8") (pintype "bidirectional"))
    )
    (net (code "38") (name "/OUT1_C") (class "Default")
      (node (ref "P4") (pin "2") (pinfunction "GND_2") (pintype "passive"))
      (node (ref "U6") (pin "8") (pinfunction "OUT1_8") (pintype "bidirectional"))
    )
    (net (code "39") (name "/OUT2_A") (class "Default")
      (node (ref "P2") (pin "1") (pinfunction "VCC_1") (pintype "passive"))
      (node (ref "U4") (pin "10") (pinfunction "OUT2_10") (pintype "bidirectional"))
    )
    (net (code "40") (name "/OUT2_B") (class "Default")
      (node (ref "P3") (pin "1") (pinfunction "VCC_1") (pintype "passive"))
      (node (ref "U5") (pin "10") (pinfunction "OUT2_10") (pintype "bidirectional"))
    )
    (net (code "41") (name "/OUT2_C") (class "Default")
      (node (ref "P4") (pin "1") (pinfunction "VCC_1") (pintype "passive"))
      (node (ref "U6") (pin "10") (pinfunction "OUT2_10") (pintype "bidirectional"))
    )
    (net (code "42") (name "/RESET") (class "Default")
      (node (ref "C27") (pin "2") (pinfunction "2_2") (pintype "passive"))
      (node (ref "R3") (pin "2") (pinfunction "2_2") (pintype "passive"))
      (node (ref "U2") (pin "38") (pinfunction "RESET_38") (pintype "input"))
    )
    (net (code "43") (name "/SHIELD") (class "Default")
      (node (ref "C2") (pin "2") (pinfunction "2_2") (pintype "passive"))
      (node (ref "R1") (pin "2") (pinfunction "2_2") (pintype "passive"))
      (node (ref "USB1") (pin "5") (pinfunction "SHIELD_5") (pintype "passive"))
      (node (ref "USB1") (pin "6") (pinfunction "SHIELD_6") (pintype "passive"))
    )
    (net (code "44") (name "/TCK") (class "Default")
      (node (ref "P1") (pin "2") (pinfunction "2_2") (pintype "passive"))
      (node (ref "R2") (pin "2") (pinfunction "2_2") (pintype "passive"))
      (node (ref "U2") (pin "52") (pinfunction "PC0/TCK/SWCLK_52") (pintype "bidirectional"))
    )
    (net (code "45") (name "/TDI") (class "Default")
      (node (ref "P1") (pin "4") (pinfunction "4_4") (pintype "passive"))
      (node (ref "U2") (pin "50") (pinfunction "PC2/TDI_50") (pintype "bidirectional"))
    )
    (net (code "46") (name "/TDO") (class "Default")
      (node (ref "P1") (pin "3") (pinfunction "3_3") (pintype "passive"))
      (node (ref "U2") (pin "49") (pinfunction "PC3/TDO/SWO_49") (pintype "bidirectional"))
    )
    (net (code "47") (name "/TMS") (class "Default")
      (node (ref "P1") (pin "5") (pinfunction "5_5") (pintype "passive"))
      (node (ref "U2") (pin "51") (pinfunction "PC1/TMS/SWDIO_51") (pintype "bidirectional"))
    )
    (net (code "48") (name "/USB RX LED") (class "Default")
      (node (ref "D2") (pin "2") (pinfunction "K_2") (pintype "passive"))
      (node (ref "U3") (pin "5") (pinfunction "CBUS2_5") (pintype "passive"))
    )
    (net (code "49") (name "/USB TX LED") (class "Default")
      (node (ref "D1") (pin "2") (pinfunction "K_2") (pintype "passive"))
      (node (ref "U3") (pin "11") (pinfunction "CBUS1_11") (pintype "passive"))
    )
    (net (code "50") (name "/USB_RX") (class "Default")
      (node (ref "R4") (pin "1") (pinfunction "1_1") (pintype "passive"))
      (node (ref "U2") (pin "17") (pinfunction "PA0/U0RX_17") (pintype "bidirectional"))
      (node (ref "U3") (pin "15") (pinfunction "TXD_15") (pintype "passive"))
    )
    (net (code "51") (name "/USB_TX") (class "Default")
      (node (ref "R5") (pin "1") (pinfunction "1_1") (pintype "passive"))
      (node (ref "U2") (pin "18") (pinfunction "PA1/U0TX_18") (pintype "bidirectional"))
      (node (ref "U3") (pin "2") (pinfunction "RXD_2") (pintype "passive"))
    )
    (net (code "52") (name "/VCORE") (class "Default")
      (node (ref "C24") (pin "2") (pinfunction "2_2") (pintype "passive"))
      (node (ref "C25") (pin "2") (pinfunction "2_2") (pintype "passive"))
      (node (ref "C26") (pin "2") (pinfunction "2_2") (pintype "passive"))
      (node (ref "U2") (pin "25") (pinfunction "VDDC_25") (pintype "power_in"))
      (node (ref "U2") (pin "56") (pinfunction "VDDC_56") (pintype "power_in"))
    )
    (net (code "53") (name "/VREF_A") (class "Default")
      (node (ref "R17") (pin "2") (pinfunction "2_2") (pintype "passive"))
      (node (ref "R18") (pin "1") (pinfunction "1_1") (pintype "passive"))
      (node (ref "U4") (pin "5") (pinfunction "VREF_5") (pintype "power_in"))
    )
    (net (code "54") (name "/VREF_B") (class "Default")
      (node (ref "R21") (pin "2") (pinfunction "2_2") (pintype "passive"))
      (node (ref "R22") (pin "1") (pinfunction "1_1") (pintype "passive"))
      (node (ref "U5") (pin "5") (pinfunction "VREF_5") (pintype "power_in"))
    )
    (net (code "55") (name "/VREF_C") (class "Default")
      (node (ref "R25") (pin "2") (pinfunction "2_2") (pintype "passive"))
      (node (ref "R26") (pin "1") (pinfunction "1_1") (pintype "passive"))
      (node (ref "U6") (pin "5") (pinfunction "VREF_5") (pintype "power_in"))
    )
    (net (code "56") (name "/nFLT_A") (class "Default")
      (node (ref "R15") (pin "1") (pinfunction "1_1") (pintype "passive"))
      (node (ref "U2") (pin "31") (pinfunction "PF3_31") (pintype "bidirectional"))
      (node (ref "U4") (pin "4") (pinfunction "nFAULT_4") (pintype "bidirectional"))
    )
    (net (code "57") (name "/nFLT_B") (class "Default")
      (node (ref "R19") (pin "2") (pinfunction "2_2") (pintype "passive"))
      (node (ref "U2") (pin "23") (pinfunction "PA6_23") (pintype "bidirectional"))
      (node (ref "U5") (pin "4") (pinfunction "nFAULT_4") (pintype "bidirectional"))
    )
    (net (code "58") (name "/nFLT_C") (class "Default")
      (node (ref "R23") (pin "2") (pinfunction "2_2") (pintype "passive"))
      (node (ref "U2") (pin "46") (pinfunction "PB1/USB0VBUS_46") (pintype "bidirectional"))
      (node (ref "U6") (pin "4") (pinfunction "nFAULT_4") (pintype "bidirectional"))
    )
    (net (code "59") (name "/nSLEEP_A") (class "Default")
      (node (ref "U2") (pin "20") (pinfunction "PA3/SSI0FSS_20") (pintype "bidirectional"))
      (node (ref "U4") (pin "3") (pinfunction "nSLEEP_3") (pintype "bidirectional"))
    )
    (net (code "60") (name "/nSLEEP_B") (class "Default")
      (node (ref "U2") (pin "29") (pinfunction "PF1_29") (pintype "bidirectional"))
      (node (ref "U5") (pin "3") (pinfunction "nSLEEP_3") (pintype "bidirectional"))
    )
    (net (code "61") (name "/nSLEEP_C") (class "Default")
      (node (ref "U2") (pin "45") (pinfunction "PB0/USB0ID_45") (pintype "bidirectional"))
      (node (ref "U6") (pin "3") (pinfunction "nSLEEP_3") (pintype "bidirectional"))
    )
    (net (code "62") (name "GND") (class "Default")
      (node (ref "C1") (pin "2") (pinfunction "2_2") (pintype "passive"))
      (node (ref "C10") (pin "2") (pinfunction "2_2") (pintype "passive"))
      (node (ref "C11") (pin "2") (pinfunction "2_2") (pintype "passive"))
      (node (ref "C12") (pin "2") (pinfunction "2_2") (pintype "passive"))
      (node (ref "C13") (pin "1") (pinfunction "1_1") (pintype "passive"))
      (node (ref "C14") (pin "1") (pinfunction "1_1") (pintype "passive"))
      (node (ref "C15") (pin "1") (pinfunction "1_1") (pintype "passive"))
      (node (ref "C16") (pin "1") (pinfunction "1_1") (pintype "passive"))
      (node (ref "C17") (pin "1") (pinfunction "1_1") (pintype "passive"))
      (node (ref "C18") (pin "1") (pinfunction "1_1") (pintype "passive"))
      (node (ref "C19") (pin "1") (pinfunction "1_1") (pintype "passive"))
      (node (ref "C2") (pin "1") (pinfunction "1_1") (pintype "passive"))
      (node (ref "C20") (pin "1") (pinfunction "1_1") (pintype "passive"))
      (node (ref "C21") (pin "1") (pinfunction "1_1") (pintype "passive"))
      (node (ref "C22") (pin "1") (pinfunction "1_1") (pintype "passive"))
      (node (ref "C23") (pin "1") (pinfunction "1_1") (pintype "passive"))
      (node (ref "C24") (pin "1") (pinfunction "1_1") (pintype "passive"))
      (node (ref "C25") (pin "1") (pinfunction "1_1") (pintype "passive"))
      (node (ref "C26") (pin "1") (pinfunction "1_1") (pintype "passive"))
      (node (ref "C27") (pin "1") (pinfunction "1_1") (pintype "passive"))
      (node (ref "C28") (pin "1") (pinfunction "1_1") (pintype "passive"))
      (node (ref "C29") (pin "1") (pinfunction "1_1") (pintype "passive"))
      (node (ref "C3") (pin "1") (pinfunction "1_1") (pintype "passive"))
      (node (ref "C32") (pin "1") (pinfunction "1_1") (pintype "passive"))
      (node (ref "C33") (pin "1") (pinfunction "1_1") (pintype "passive"))
      (node (ref "C36") (pin "1") (pinfunction "1_1") (pintype "passive"))
      (node (ref "C37") (pin "1") (pinfunction "1_1") (pintype "passive"))
      (node (ref "C4") (pin "1") (pinfunction "1_1") (pintype "passive"))
      (node (ref "C40") (pin "1") (pinfunction "1_1") (pintype "passive"))
      (node (ref "C41") (pin "1") (pinfunction "1_1") (pintype "passive"))
      (node (ref "C5") (pin "1") (pinfunction "1_1") (pintype "passive"))
      (node (ref "C6") (pin "1") (pinfunction "1_1") (pintype "passive"))
      (node (ref "C7") (pin "2") (pinfunction "2_2") (pintype "passive"))
      (node (ref "C8") (pin "2") (pinfunction "2_2") (pintype "passive"))
      (node (ref "C9") (pin "1") (pinfunction "1_1") (pintype "passive"))
      (node (ref "P1") (pin "1") (pinfunction "1_1") (pintype "passive"))
      (node (ref "P5") (pin "6") (pinfunction "GND_6") (pintype "passive"))
      (node (ref "P6") (pin "6") (pinfunction "GND_6") (pintype "passive"))
      (node (ref "P8") (pin "1") (pinfunction "1_1") (pintype "passive"))
      (node (ref "P8") (pin "2") (pinfunction "2_2") (pintype "passive"))
      (node (ref "P8") (pin "3") (pinfunction "3_3") (pintype "passive"))
      (node (ref "P9") (pin "1") (pinfunction "1_1") (pintype "passive"))
      (node (ref "P9") (pin "2") (pinfunction "2_2") (pintype "passive"))
      (node (ref "P9") (pin "3") (pinfunction "3_3") (pintype "passive"))
      (node (ref "P9") (pin "4") (pinfunction "4_4") (pintype "passive"))
      (node (ref "P9") (pin "5") (pinfunction "5_5") (pintype "passive"))
      (node (ref "P9") (pin "6") (pinfunction "6_6") (pintype "passive"))
      (node (ref "R1") (pin "1") (pinfunction "1_1") (pintype "passive"))
      (node (ref "R16") (pin "2") (pinfunction "2_2") (pintype "passive"))
      (node (ref "R18") (pin "2") (pinfunction "2_2") (pintype "passive"))
      (node (ref "R20") (pin "2") (pinfunction "2_2") (pintype "passive"))
      (node (ref "R22") (pin "2") (pinfunction "2_2") (pintype "passive"))
      (node (ref "R24") (pin "2") (pinfunction "2_2") (pintype "passive"))
      (node (ref "R26") (pin "2") (pinfunction "2_2") (pintype "passive"))
      (node (ref "U1") (pin "2") (pinfunction "GND_2") (pintype "power_in"))
      (node (ref "U1") (pin "4") (pinfunction "GND_4") (pintype "power_in"))
      (node (ref "U2") (pin "12") (pinfunction "GND_12") (pintype "power_in"))
      (node (ref "U2") (pin "27") (pinfunction "GND_27") (pintype "power_in"))
      (node (ref "U2") (pin "3") (pinfunction "GNDA_3") (pintype "power_in"))
      (node (ref "U2") (pin "32") (pinfunction "WAKE_32") (pintype "input"))
      (node (ref "U2") (pin "34") (pinfunction "XOSC0_34") (pintype "input"))
      (node (ref "U2") (pin "35") (pinfunction "GNDX_35") (pintype "power_in"))
      (node (ref "U2") (pin "39") (pinfunction "GND_39") (pintype "power_in"))
      (node (ref "U2") (pin "55") (pinfunction "GND_55") (pintype "power_in"))
      (node (ref "U3") (pin "13") (pinfunction "GND_13") (pintype "passive"))
      (node (ref "U3") (pin "17") (pinfunction "GND_17") (pintype "passive"))
      (node (ref "U3") (pin "3") (pinfunction "GND_3") (pintype "passive"))
      (node (ref "U4") (pin "15") (pinfunction "GND_15") (pintype "passive"))
      (node (ref "U4") (pin "16") (pinfunction "PMODE_16") (pintype "bidirectional"))
      (node (ref "U4") (pin "7") (pinfunction "IMODE_7") (pintype "bidirectional"))
      (node (ref "U4") (pin "9") (pinfunction "PGND_9") (pintype "passive"))
      (node (ref "U5") (pin "15") (pinfunction "GND_15") (pintype "passive"))
      (node (ref "U5") (pin "16") (pinfunction "PMODE_16") (pintype "bidirectional"))
      (node (ref "U5") (pin "7") (pinfunction "IMODE_7") (pintype "bidirectional"))
      (node (ref "U5") (pin "9") (pinfunction "PGND_9") (pintype "passive"))
      (node (ref "U6") (pin "15") (pinfunction "GND_15") (pintype "passive"))
      (node (ref "U6") (pin "16") (pinfunction "PMODE_16") (pintype "bidirectional"))
      (node (ref "U6") (pin "7") (pinfunction "IMODE_7") (pintype "bidirectional"))
      (node (ref "U6") (pin "9") (pinfunction "PGND_9") (pintype "passive"))
      (node (ref "U7") (pin "4") (pinfunction "GND_4") (pintype "power_in"))
      (node (ref "U8") (pin "4") (pinfunction "GND_4") (pintype "power_in"))
      (node (ref "USB1") (pin "4") (pinfunction "GND_4") (pintype "power_in"))
      (node (ref "X1") (pin "2") (pinfunction "CASE_2") (pintype "passive"))
      (node (ref "X1") (pin "4") (pinfunction "CASE_4") (pintype "passive"))
    )
    (net (code "63") (name "Net-(D1-A)") (class "Default")
      (node (ref "D1") (pin "1") (pinfunction "A_1") (pintype "passive"))
      (node (ref "R13") (pin "1") (pinfunction "1_1") (pintype "passive"))
    )
    (net (code "64") (name "Net-(D2-A)") (class "Default")
      (node (ref "D2") (pin "1") (pinfunction "A_1") (pintype "passive"))
      (node (ref "R14") (pin "1") (pinfunction "1_1") (pintype "passive"))
    )
    (net (code "65") (name "Net-(U3-CTS#)") (class "Default")
      (node (ref "R7") (pin "1") (pinfunction "1_1") (pintype "passive"))
      (node (ref "U3") (pin "4") (pinfunction "CTS#_4") (pintype "passive"))
    )
    (net (code "66") (name "Net-(U3-RTS#)") (class "Default")
      (node (ref "R6") (pin "1") (pinfunction "1_1") (pintype "passive"))
      (node (ref "U3") (pin "16") (pinfunction "RTS#_16") (pintype "passive"))
    )
    (net (code "67") (name "Net-(U3-USBDM)") (class "Default")
      (node (ref "R8") (pin "2") (pinfunction "2_2") (pintype "passive"))
      (node (ref "U3") (pin "7") (pinfunction "USBDM_7") (pintype "passive"))
    )
    (net (code "68") (name "Net-(U3-USBDP)") (class "Default")
      (node (ref "R9") (pin "2") (pinfunction "2_2") (pintype "passive"))
      (node (ref "U3") (pin "6") (pinfunction "USBDP_6") (pintype "passive"))
    )
    (net (code "69") (name "Net-(U4-CPH)") (class "Default")
      (node (ref "C30") (pin "2") (pinfunction "2_2") (pintype "passive"))
      (node (ref "U4") (pin "13") (pinfunction "CPH_13") (pintype "passive"))
    )
    (net (code "70") (name "Net-(U4-CPL)") (class "Default")
      (node (ref "C30") (pin "1") (pinfunction "1_1") (pintype "passive"))
      (node (ref "U4") (pin "14") (pinfunction "CPL_14") (pintype "passive"))
    )
    (net (code "71") (name "Net-(U4-VCP)") (class "Default")
      (node (ref "C31") (pin "1") (pinfunction "1_1") (pintype "passive"))
      (node (ref "U4") (pin "12") (pinfunction "VCP_12") (pintype "power_in"))
    )
    (net (code "72") (name "Net-(U5-CPH)") (class "Default")
      (node (ref "C34") (pin "2") (pinfunction "2_2") (pintype "passive"))
      (node (ref "U5") (pin "13") (pinfunction "CPH_13") (pintype "passive"))
    )
    (net (code "73") (name "Net-(U5-CPL)") (class "Default")
      (node (ref "C34") (pin "1") (pinfunction "1_1") (pintype "passive"))
      (node (ref "U5") (pin "14") (pinfunction "CPL_14") (pintype "passive"))
    )
    (net (code "74") (name "Net-(U5-VCP)") (class "Default")
      (node (ref "C35") (pin "1") (pinfunction "1_1") (pintype "passive"))
      (node (ref "U5") (pin "12") (pinfunction "VCP_12") (pintype "power_in"))
    )
    (net (code "75") (name "Net-(U6-CPH)") (class "Default")
      (node (ref "C38") (pin "2") (pinfunction "2_2") (pintype "passive"))
      (node (ref "U6") (pin "13") (pinfunction "CPH_13") (pintype "passive"))
    )
    (net (code "76") (name "Net-(U6-CPL)") (class "Default")
      (node (ref "C38") (pin "1") (pinfunction "1_1") (pintype "passive"))
      (node (ref "U6") (pin "14") (pinfunction "CPL_14") (pintype "passive"))
    )
    (net (code "77") (name "Net-(U6-VCP)") (class "Default")
      (node (ref "C39") (pin "1") (pinfunction "1_1") (pintype "passive"))
      (node (ref "U6") (pin "12") (pinfunction "VCP_12") (pintype "power_in"))
    )
    (net (code "78") (name "VBUS") (class "Default")
      (node (ref "C1") (pin "1") (pinfunction "1_1") (pintype "passive"))
      (node (ref "C3") (pin "2") (pinfunction "2_2") (pintype "passive"))
      (node (ref "L1") (pin "1") (pinfunction "1_1") (pintype "passive"))
      (node (ref "USB1") (pin "1") (pinfunction "VDD_1") (pintype "power_in"))
    )
    (net (code "79") (name "unconnected-(U2-HIB-Pad33)") (class "Default")
      (node (ref "U2") (pin "33") (pinfunction "HIB_33") (pintype "output+no_connect"))
    )
    (net (code "80") (name "unconnected-(U2-PA5{slash}SSI0TX-Pad22)") (class "Default")
      (node (ref "U2") (pin "22") (pinfunction "PA5/SSI0TX_22") (pintype "bidirectional"))
    )
    (net (code "81") (name "unconnected-(U2-PA7-Pad24)") (class "Default")
      (node (ref "U2") (pin "24") (pinfunction "PA7_24") (pintype "bidirectional"))
    )
    (net (code "82") (name "unconnected-(U2-PB5-Pad57)") (class "Default")
      (node (ref "U2") (pin "57") (pinfunction "PB5_57") (pintype "bidirectional"))
    )
    (net (code "83") (name "unconnected-(U2-PB6-Pad1)") (class "Default")
      (node (ref "U2") (pin "1") (pinfunction "PB6_1") (pintype "bidirectional"))
    )
    (net (code "84") (name "unconnected-(U2-PB7-Pad4)") (class "Default")
      (node (ref "U2") (pin "4") (pinfunction "PB7_4") (pintype "bidirectional"))
    )
    (net (code "85") (name "unconnected-(U2-PD0-Pad61)") (class "Default")
      (node (ref "U2") (pin "61") (pinfunction "PD0_61") (pintype "bidirectional"))
    )
    (net (code "86") (name "unconnected-(U2-PD4-Pad43)") (class "Default")
      (node (ref "U2") (pin "43") (pinfunction "PD4_43") (pintype "bidirectional"))
    )
    (net (code "87") (name "unconnected-(U2-PD5-Pad44)") (class "Default")
      (node (ref "U2") (pin "44") (pinfunction "PD5_44") (pintype "bidirectional"))
    )
    (net (code "88") (name "unconnected-(U2-PD6-Pad53)") (class "Default")
      (node (ref "U2") (pin "53") (pinfunction "PD6_53") (pintype "bidirectional"))
    )
    (net (code "89") (name "unconnected-(U2-PD7-Pad10)") (class "Default")
      (node (ref "U2") (pin "10") (pinfunction "PD7_10") (pintype "bidirectional"))
    )
    (net (code "90") (name "unconnected-(U2-PE0-Pad9)") (class "Default")
      (node (ref "U2") (pin "9") (pinfunction "PE0_9") (pintype "bidirectional"))
    )
    (net (code "91") (name "unconnected-(U2-PF4-Pad5)") (class "Default")
      (node (ref "U2") (pin "5") (pinfunction "PF4_5") (pintype "bidirectional"))
    )
    (net (code "92") (name "unconnected-(U2-XOSC1-Pad36)") (class "Default")
      (node (ref "U2") (pin "36") (pinfunction "XOSC1_36") (pintype "output+no_connect"))
    )
    (net (code "93") (name "unconnected-(U3-CBUS0-Pad12)") (class "Default")
      (node (ref "U3") (pin "12") (pinfunction "CBUS0_12") (pintype "passive+no_connect"))
    )
    (net (code "94") (name "unconnected-(U3-CBUS3-Pad14)") (class "Default")
      (node (ref "U3") (pin "14") (pinfunction "CBUS3_14") (pintype "passive+no_connect"))
    )
  )
)
